# U_I_Meter_TOP.net
KiCad netlist of a schematic drawn in Altium Designer
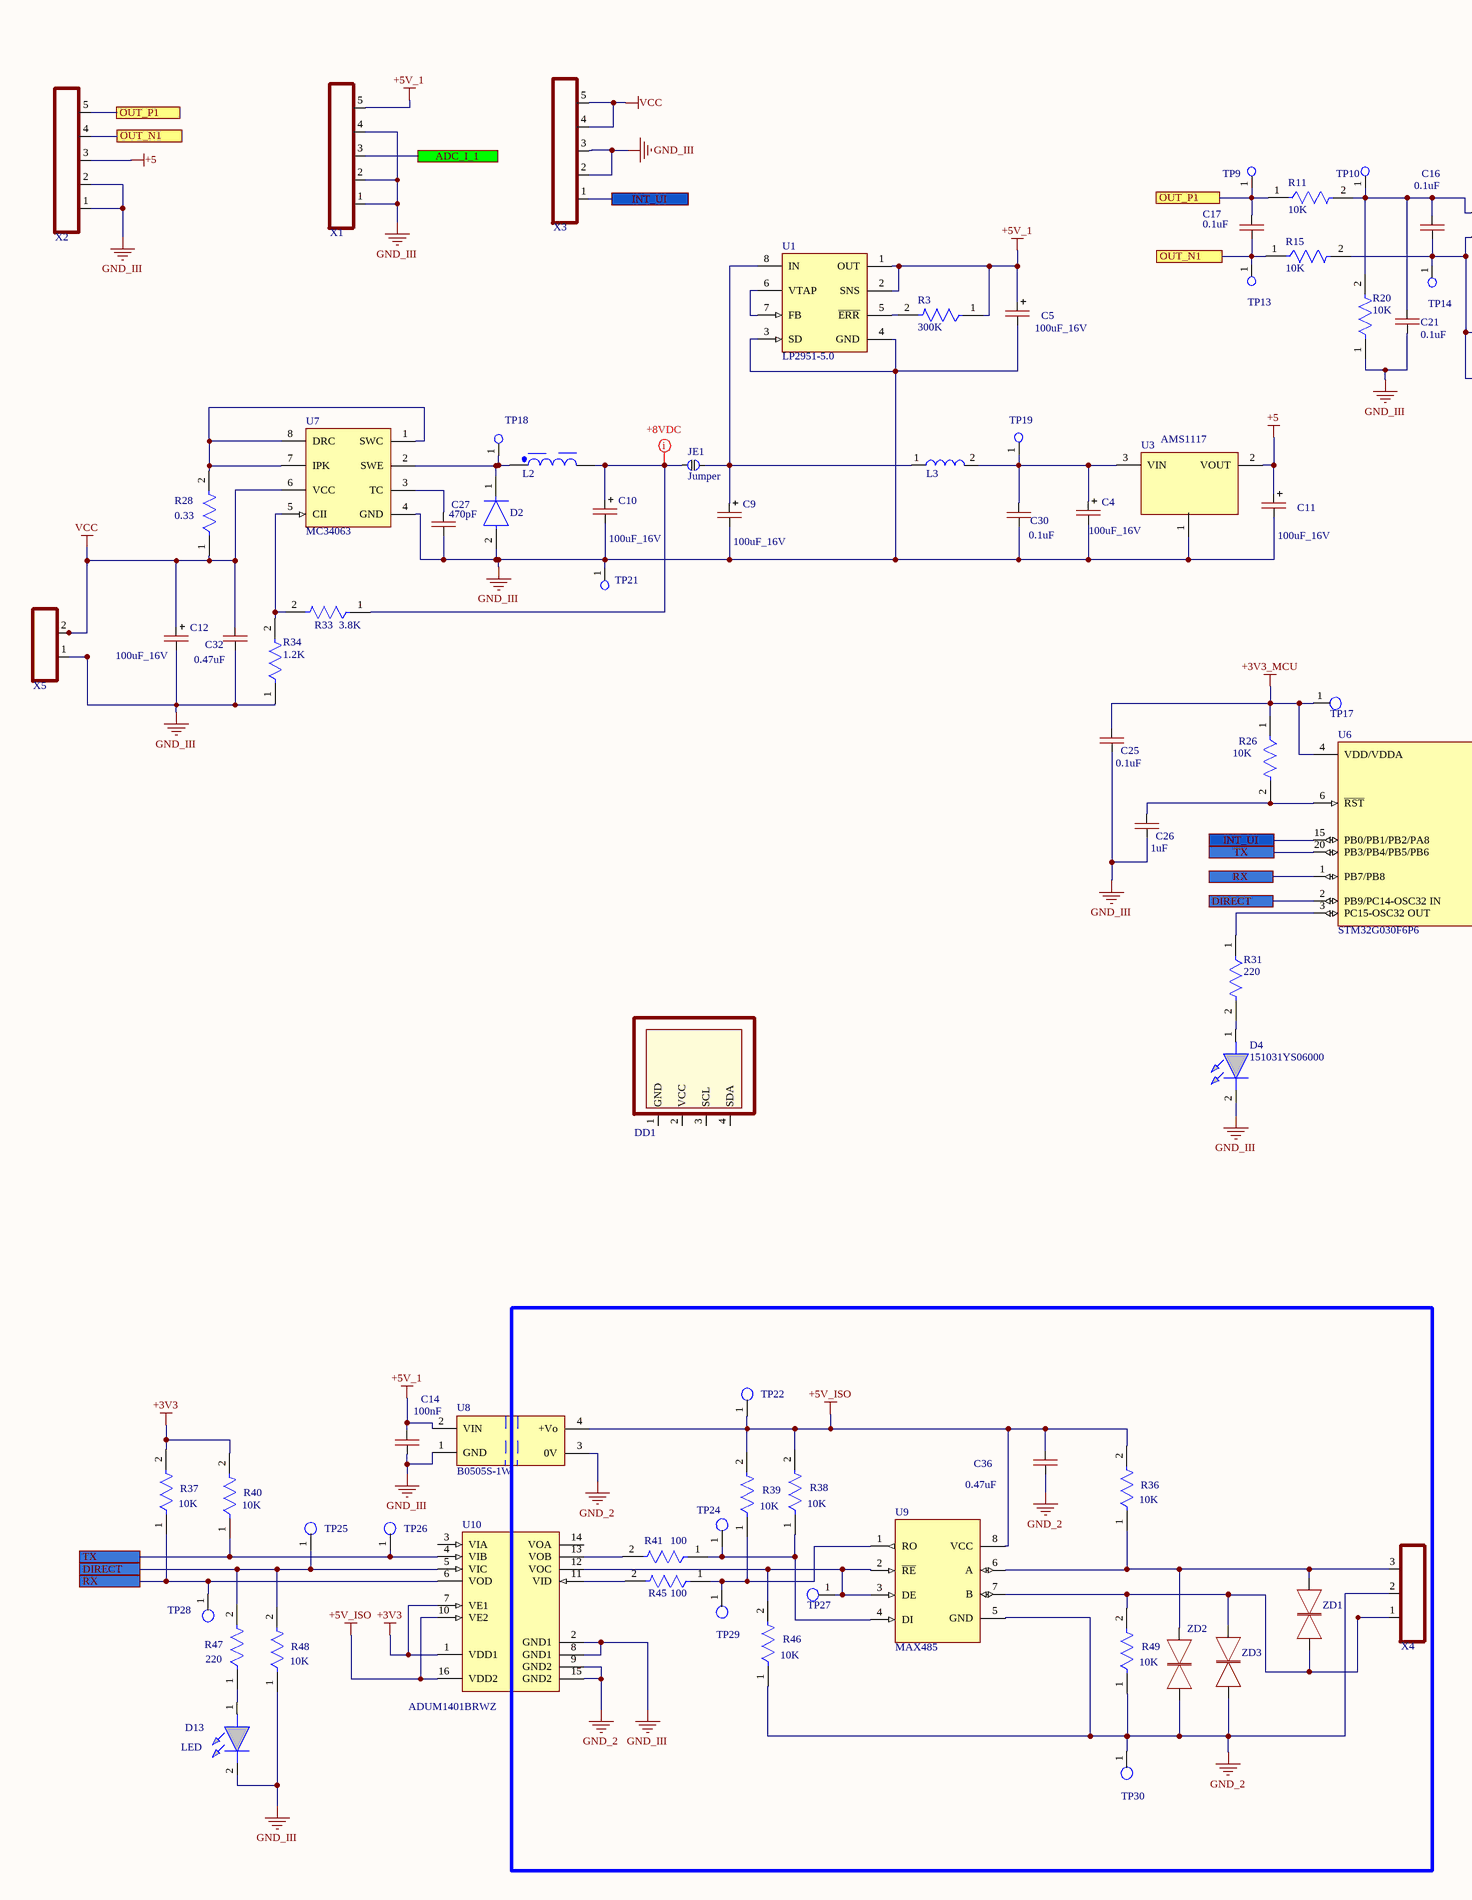
[diagram p0: U_I_Meter_TOP.SchDoc, left]
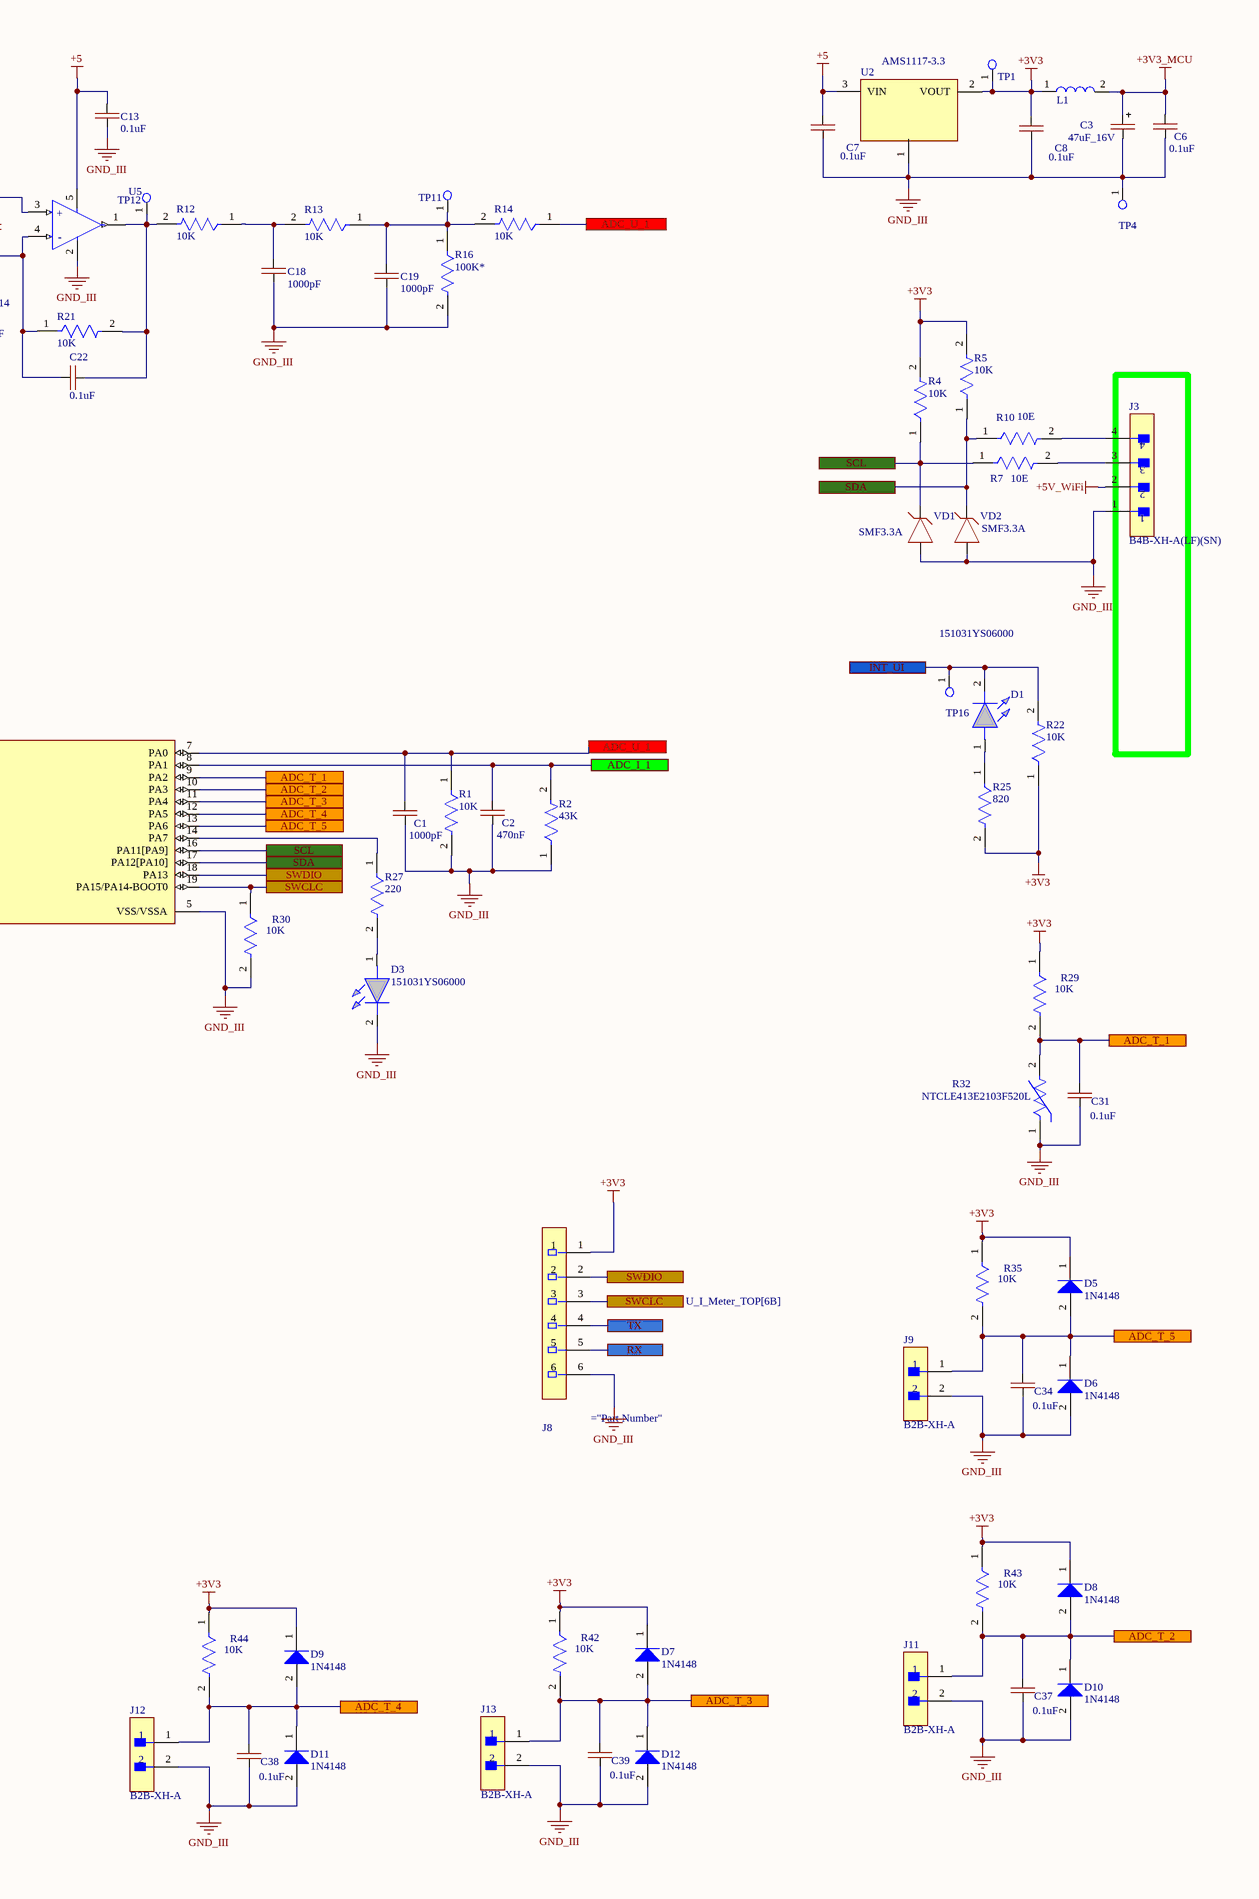
[diagram p1: U_I_Meter_TOP.SchDoc, right]

(export (version "E")
  (design (tool "Eeschema 10.0.6"))
  (components
    (comp (ref "C1")
      (value "1000pF")
      (footprint "CAP-0805")
      (libsource (lib "PASSIVE_COMPONENTS") (part "CAP-NON-POLAR"))
    )
    (comp (ref "C2")
      (value "470nF")
      (footprint "CAP-0805")
      (libsource (lib "PASSIVE_COMPONENTS") (part "CAP-NON-POLAR"))
    )
    (comp (ref "C3")
      (value "47uF_16V")
      (footprint "CAP-TAN-D")
      (libsource (lib "PASSIVE_COMPONENTS") (part "CAP-POLAR"))
    )
    (comp (ref "C4")
      (value "100uF_16V")
      (footprint "CAP-TAN-D")
      (libsource (lib "PASSIVE_COMPONENTS") (part "CAP_POL_SMD"))
    )
    (comp (ref "C5")
      (value "100uF_16V")
      (footprint "CAP-TAN-D")
      (libsource (lib "PASSIVE_COMPONENTS") (part "CAP_POL_SMD"))
    )
    (comp (ref "C6")
      (value "0.1uF")
      (footprint "CAP-0805")
      (libsource (lib "PASSIVE_COMPONENTS") (part "CAP-NON-POLAR"))
    )
    (comp (ref "C7")
      (value "0.1uF")
      (footprint "CAP-0805")
      (libsource (lib "PASSIVE_COMPONENTS") (part "CAP-NON-POLAR"))
    )
    (comp (ref "C8")
      (value "0.1uF")
      (footprint "CAP-0805")
      (libsource (lib "PASSIVE_COMPONENTS") (part "CAP-NON-POLAR"))
    )
    (comp (ref "C9")
      (value "100uF_16V")
      (footprint "CAP-TAN-D")
      (libsource (lib "PASSIVE_COMPONENTS") (part "CAP_POL_SMD"))
    )
    (comp (ref "C10")
      (value "100uF_16V")
      (footprint "CAP-TAN-D")
      (libsource (lib "PASSIVE_COMPONENTS") (part "CAP_POL_SMD"))
    )
    (comp (ref "C11")
      (value "100uF_16V")
      (footprint "CAP-TAN-D")
      (libsource (lib "PASSIVE_COMPONENTS") (part "CAP_POL_SMD"))
    )
    (comp (ref "C12")
      (value "100uF_16V")
      (footprint "CAP-TAN-D")
      (libsource (lib "PASSIVE_COMPONENTS") (part "CAP_POL_SMD"))
    )
    (comp (ref "C13")
      (value "0.1uF")
      (footprint "CAP-0805")
      (libsource (lib "PASSIVE_COMPONENTS") (part "CAP-NON-POLAR"))
    )
    (comp (ref "C14")
      (value "100nF")
      (footprint "CAP-0805")
      (libsource (lib "PASSIVE_COMPONENTS") (part "CAP-NON-POLAR"))
    )
    (comp (ref "C16")
      (value "0.1uF")
      (footprint "CAP-0805")
      (libsource (lib "PASSIVE_COMPONENTS") (part "CAP-NON-POLAR"))
    )
    (comp (ref "C17")
      (value "0.1uF")
      (footprint "CAP-0805")
      (libsource (lib "PASSIVE_COMPONENTS") (part "CAP-NON-POLAR"))
    )
    (comp (ref "C18")
      (value "1000pF")
      (footprint "CAP-0805")
      (libsource (lib "PASSIVE_COMPONENTS") (part "CAP-NON-POLAR"))
    )
    (comp (ref "C19")
      (value "1000pF")
      (footprint "CAP-0805")
      (libsource (lib "PASSIVE_COMPONENTS") (part "CAP-NON-POLAR"))
    )
    (comp (ref "C21")
      (value "0.1uF")
      (footprint "CAP-0805")
      (libsource (lib "PASSIVE_COMPONENTS") (part "CAP-NON-POLAR"))
    )
    (comp (ref "C22")
      (value "0.1uF")
      (footprint "CAP-0805")
      (libsource (lib "PASSIVE_COMPONENTS") (part "CAP-NON-POLAR"))
    )
    (comp (ref "C25")
      (value "0.1uF")
      (footprint "CAP-0805")
      (libsource (lib "PASSIVE_COMPONENTS") (part "CAP-NON-POLAR"))
    )
    (comp (ref "C26")
      (value "1uF")
      (footprint "CAP-0805")
      (libsource (lib "PASSIVE_COMPONENTS") (part "CAP-NON-POLAR"))
    )
    (comp (ref "C27")
      (value "470pF")
      (footprint "CAP-0805")
      (libsource (lib "PASSIVE_COMPONENTS") (part "CAP-NON-POLAR"))
    )
    (comp (ref "C30")
      (value "0.1uF")
      (footprint "CAP-0805")
      (libsource (lib "PASSIVE_COMPONENTS") (part "CAP-NON-POLAR"))
    )
    (comp (ref "C31")
      (value "0.1uF")
      (footprint "CAP-0805")
      (libsource (lib "PASSIVE_COMPONENTS") (part "CAP-NON-POLAR"))
    )
    (comp (ref "C32")
      (value "0.47uF")
      (footprint "CAP-0805")
      (libsource (lib "PASSIVE_COMPONENTS") (part "CAP-NON-POLAR"))
    )
    (comp (ref "C34")
      (value "0.1uF")
      (footprint "CAP-0805")
      (libsource (lib "PASSIVE_COMPONENTS") (part "CAP-NON-POLAR"))
    )
    (comp (ref "C36")
      (value "0.47uF")
      (footprint "CAP-0805")
      (libsource (lib "PASSIVE_COMPONENTS") (part "CAP-NON-POLAR"))
    )
    (comp (ref "C37")
      (value "0.1uF")
      (footprint "CAP-0805")
      (libsource (lib "PASSIVE_COMPONENTS") (part "CAP-NON-POLAR"))
    )
    (comp (ref "C38")
      (value "0.1uF")
      (footprint "CAP-0805")
      (libsource (lib "PASSIVE_COMPONENTS") (part "CAP-NON-POLAR"))
    )
    (comp (ref "C39")
      (value "0.1uF")
      (footprint "CAP-0805")
      (libsource (lib "PASSIVE_COMPONENTS") (part "CAP-NON-POLAR"))
    )
    (comp (ref "D1")
      (value "151031YS06000")
      (footprint "LED_3mm_BLUE")
      (description "WURTH ELEKTRONIK - 151031YS06000 - LED, Yellow, Through Hole, T-1 (3mm), 30 mA, 2 V, 590 nm")
      (fields (field (name "MOUSER PART NUMBER") "710-151031YS06000"))
      (libsource (lib "Optic-LED") (part "LED"))
    )
    (comp (ref "D2")
      (value "ES1G")
      (footprint "FP-403AE-MFG")
      (description "Ultrafast")
      (libsource (lib "Diodes") (part "ES1G"))
    )
    (comp (ref "D3")
      (value "151031YS06000")
      (footprint "LED_3mm_GREEN")
      (description "WURTH ELEKTRONIK - 151031YS06000 - LED, Yellow, Through Hole, T-1 (3mm), 30 mA, 2 V, 590 nm")
      (fields (field (name "MOUSER PART NUMBER") "710-151031YS06000"))
      (libsource (lib "Optic-LED") (part "LED"))
    )
    (comp (ref "D4")
      (value "151031YS06000")
      (footprint "LED_3mm_RED")
      (description "WURTH ELEKTRONIK - 151031YS06000 - LED, Yellow, Through Hole, T-1 (3mm), 30 mA, 2 V, 590 nm")
      (fields (field (name "MOUSER PART NUMBER") "710-151031YS06000"))
      (libsource (lib "Optic-LED") (part "LED"))
    )
    (comp (ref "D5")
      (value "1N4148")
      (footprint "DIOD-SOD123-2_V")
      (libsource (lib "Diodes") (part "1N4148"))
    )
    (comp (ref "D6")
      (value "1N4148")
      (footprint "DIOD-SOD123-2_V")
      (libsource (lib "Diodes") (part "1N4148"))
    )
    (comp (ref "D7")
      (value "1N4148")
      (footprint "DIOD-SOD123-2_V")
      (libsource (lib "Diodes") (part "1N4148"))
    )
    (comp (ref "D8")
      (value "1N4148")
      (footprint "DIOD-SOD123-2_V")
      (libsource (lib "Diodes") (part "1N4148"))
    )
    (comp (ref "D9")
      (value "1N4148")
      (footprint "DIOD-SOD123-2_V")
      (libsource (lib "Diodes") (part "1N4148"))
    )
    (comp (ref "D10")
      (value "1N4148")
      (footprint "DIOD-SOD123-2_V")
      (libsource (lib "Diodes") (part "1N4148"))
    )
    (comp (ref "D11")
      (value "1N4148")
      (footprint "DIOD-SOD123-2_V")
      (libsource (lib "Diodes") (part "1N4148"))
    )
    (comp (ref "D12")
      (value "1N4148")
      (footprint "DIOD-SOD123-2_V")
      (libsource (lib "Diodes") (part "1N4148"))
    )
    (comp (ref "D13")
      (value "LED")
      (footprint "LED_3mm_BLUE")
      (description "WURTH ELEKTRONIK - 151031YS06000 - LED, Yellow, Through Hole, T-1 (3mm), 30 mA, 2 V, 590 nm")
      (fields
        (field (name "MANUFACTURER_PART_NUMBER") "151031YS06000")
        (field (name "MOUSER PART NUMBER") "710-151031YS06000")
      )
      (libsource (lib "Optic-LED") (part "LED"))
    )
    (comp (ref "DD1")
      (value "OLED_SSD_1306")
      (footprint "OLED_128x64_SSD_1306")
      (libsource (lib "Displays") (part "OLED_SSD_1306"))
    )
    (comp (ref "J3")
      (value "B4B-XH-A(LF)(SN)")
      (footprint "B4B-XH-A")
      (libsource (lib "Connectors") (part "B4B-XH-A(LF)(SN)"))
    )
    (comp (ref "J8")
      (value "SWR25X-NRTC-S06-ST-BA")
      (footprint "Sullins_SWR25X-NRTC-S06-ST-BA_MFG")
      (libsource (lib "Conn_Sullins_SWR25X-NRTC-S06-ST-BA_eec") (part "SWR25X-NRTC-S06-ST-BA"))
    )
    (comp (ref "J9")
      (value "B2B-XH-A")
      (footprint "B2B-XH-A")
      (libsource (lib "Connectors") (part "B2B-XH-A"))
    )
    (comp (ref "J11")
      (value "B2B-XH-A")
      (footprint "B2B-XH-A")
      (libsource (lib "Connectors") (part "B2B-XH-A"))
    )
    (comp (ref "J12")
      (value "B2B-XH-A")
      (footprint "B2B-XH-A")
      (libsource (lib "Connectors") (part "B2B-XH-A"))
    )
    (comp (ref "J13")
      (value "B2B-XH-A")
      (footprint "B2B-XH-A")
      (libsource (lib "Connectors") (part "B2B-XH-A"))
    )
    (comp (ref "JE1") (value "Jumper") (footprint "JE") (libsource (lib "Connectors") (part "JE")))
    (comp (ref "L1")
      (value "Coil")
      (footprint "Coil_4.5x4.5_mm")
      (libsource (lib "Transformers") (part "Coil"))
    )
    (comp (ref "L2")
      (value "3.3µH, 4A")
      (footprint "WE-PD2_5848")
      (description "WE-PD2 SMT Power Inductor, size 5848, 3.3µH, 4A, 0.06Ω")
      (fields
        (field (name "MANUFACTURER PART NUMBER") "744774033")
        (field (name "MANUFACTURER") "Wurth Elektronik")
      )
      (libsource (lib "WE-PD2 (rev22d)") (part "744774033"))
    )
    (comp (ref "L3")
      (value "Coil")
      (footprint "Coil_4.5x4.5_mm")
      (libsource (lib "Transformers") (part "Coil"))
    )
    (comp (ref "R1")
      (value "10K")
      (footprint "RES-0805")
      (libsource (lib "PASSIVE_COMPONENTS") (part "RES-CONST"))
    )
    (comp (ref "R2")
      (value "43K")
      (footprint "RES-0805")
      (libsource (lib "PASSIVE_COMPONENTS") (part "RES-CONST"))
    )
    (comp (ref "R3")
      (value "300K")
      (footprint "RES-0805")
      (libsource (lib "PASSIVE_COMPONENTS") (part "RES-CONST"))
    )
    (comp (ref "R4")
      (value "10K")
      (footprint "RES-0805")
      (libsource (lib "PASSIVE_COMPONENTS") (part "RES-CONST"))
    )
    (comp (ref "R5")
      (value "10K")
      (footprint "RES-0805")
      (libsource (lib "PASSIVE_COMPONENTS") (part "RES-CONST"))
    )
    (comp (ref "R7")
      (value "10E")
      (footprint "RES-0805")
      (libsource (lib "PASSIVE_COMPONENTS") (part "RES-CONST"))
    )
    (comp (ref "R10")
      (value "10E")
      (footprint "RES-0805")
      (libsource (lib "PASSIVE_COMPONENTS") (part "RES-CONST"))
    )
    (comp (ref "R11")
      (value "10K")
      (footprint "RES-0805")
      (libsource (lib "PASSIVE_COMPONENTS") (part "RES-CONST"))
    )
    (comp (ref "R12")
      (value "10K")
      (footprint "RES-0805")
      (libsource (lib "PASSIVE_COMPONENTS") (part "RES-CONST"))
    )
    (comp (ref "R13")
      (value "10K")
      (footprint "RES-0805")
      (libsource (lib "PASSIVE_COMPONENTS") (part "RES-CONST"))
    )
    (comp (ref "R14")
      (value "10K")
      (footprint "RES-0805")
      (libsource (lib "PASSIVE_COMPONENTS") (part "RES-CONST"))
    )
    (comp (ref "R15")
      (value "10K")
      (footprint "RES-0805")
      (libsource (lib "PASSIVE_COMPONENTS") (part "RES-CONST"))
    )
    (comp (ref "R16")
      (value "100K*")
      (footprint "RES-0805")
      (libsource (lib "PASSIVE_COMPONENTS") (part "RES-CONST"))
    )
    (comp (ref "R20")
      (value "10K")
      (footprint "RES-0805")
      (libsource (lib "PASSIVE_COMPONENTS") (part "RES-CONST"))
    )
    (comp (ref "R21")
      (value "10K")
      (footprint "RES-0805")
      (libsource (lib "PASSIVE_COMPONENTS") (part "RES-CONST"))
    )
    (comp (ref "R22")
      (value "10K")
      (footprint "RES-0805")
      (libsource (lib "PASSIVE_COMPONENTS") (part "RES-CONST"))
    )
    (comp (ref "R25")
      (value "820")
      (footprint "RES-0805")
      (description "220")
      (libsource (lib "PASSIVE_COMPONENTS") (part "RES-CONST"))
    )
    (comp (ref "R26")
      (value "10K")
      (footprint "RES-0805")
      (libsource (lib "PASSIVE_COMPONENTS") (part "RES-CONST"))
    )
    (comp (ref "R27")
      (value "220")
      (footprint "RES-0805")
      (libsource (lib "PASSIVE_COMPONENTS") (part "RES-CONST"))
    )
    (comp (ref "R28")
      (value "0.33")
      (footprint "RES-1206")
      (libsource (lib "PASSIVE_COMPONENTS") (part "RES-CONST"))
    )
    (comp (ref "R29")
      (value "10K")
      (footprint "RES-0805")
      (libsource (lib "PASSIVE_COMPONENTS") (part "RES-CONST"))
    )
    (comp (ref "R30")
      (value "10K")
      (footprint "RES-0805")
      (libsource (lib "PASSIVE_COMPONENTS") (part "RES-CONST"))
    )
    (comp (ref "R31")
      (value "220")
      (footprint "RES-0805")
      (libsource (lib "PASSIVE_COMPONENTS") (part "RES-CONST"))
    )
    (comp (ref "R32")
      (value "NTCLE413E2103F520L")
      (footprint "FP-NTCLE413E2103F520L-MFG")
      (description "THERMISTOR NTC 10KOHM 3435K BEAD")
      (fields (field (name "TOLERANCE") "1%"))
      (libsource (lib "Altium Content Vault") (part "3b148a6ebabc5fb4d708a66c052d352"))
    )
    (comp (ref "R33")
      (value "3.8K")
      (footprint "RES-0805")
      (description "10K")
      (libsource (lib "PASSIVE_COMPONENTS") (part "RES-CONST"))
    )
    (comp (ref "R34")
      (value "1.2K")
      (footprint "RES-0805")
      (libsource (lib "PASSIVE_COMPONENTS") (part "RES-CONST"))
    )
    (comp (ref "R35")
      (value "10K")
      (footprint "RES-0805")
      (libsource (lib "PASSIVE_COMPONENTS") (part "RES-CONST"))
    )
    (comp (ref "R36")
      (value "10K")
      (footprint "RES-0805")
      (libsource (lib "PASSIVE_COMPONENTS") (part "RES-CONST"))
    )
    (comp (ref "R37")
      (value "10K")
      (footprint "RES-0805")
      (libsource (lib "PASSIVE_COMPONENTS") (part "RES-CONST"))
    )
    (comp (ref "R38")
      (value "10K")
      (footprint "RES-0805")
      (libsource (lib "PASSIVE_COMPONENTS") (part "RES-CONST"))
    )
    (comp (ref "R39")
      (value "10K")
      (footprint "RES-0805")
      (libsource (lib "PASSIVE_COMPONENTS") (part "RES-CONST"))
    )
    (comp (ref "R40")
      (value "10K")
      (footprint "RES-0805")
      (libsource (lib "PASSIVE_COMPONENTS") (part "RES-CONST"))
    )
    (comp (ref "R41")
      (value "100")
      (footprint "RES-0805")
      (libsource (lib "PASSIVE_COMPONENTS") (part "RES-CONST"))
    )
    (comp (ref "R42")
      (value "10K")
      (footprint "RES-0805")
      (libsource (lib "PASSIVE_COMPONENTS") (part "RES-CONST"))
    )
    (comp (ref "R43")
      (value "10K")
      (footprint "RES-0805")
      (libsource (lib "PASSIVE_COMPONENTS") (part "RES-CONST"))
    )
    (comp (ref "R44")
      (value "10K")
      (footprint "RES-0805")
      (libsource (lib "PASSIVE_COMPONENTS") (part "RES-CONST"))
    )
    (comp (ref "R45")
      (value "100")
      (footprint "RES-0805")
      (libsource (lib "PASSIVE_COMPONENTS") (part "RES-CONST"))
    )
    (comp (ref "R46")
      (value "10K")
      (footprint "RES-0805")
      (libsource (lib "PASSIVE_COMPONENTS") (part "RES-CONST"))
    )
    (comp (ref "R47")
      (value "220")
      (footprint "RES-0805")
      (libsource (lib "PASSIVE_COMPONENTS") (part "RES-CONST"))
    )
    (comp (ref "R48")
      (value "10K")
      (footprint "RES-0805")
      (libsource (lib "PASSIVE_COMPONENTS") (part "RES-CONST"))
    )
    (comp (ref "R49")
      (value "10K")
      (footprint "RES-0805")
      (libsource (lib "PASSIVE_COMPONENTS") (part "RES-CONST"))
    )
    (comp (ref "TP1")
      (value "Test_Point_PCB")
      (footprint "Test_Point")
      (description "Test_Point")
      (libsource (lib "Connectors") (part "TP_PCB?"))
    )
    (comp (ref "TP4")
      (value "Test_Point_PCB")
      (footprint "Pin_Test_Point(Pink)")
      (description "Test_Point")
      (libsource (lib "Connectors") (part "TP_PCB?"))
    )
    (comp (ref "TP9")
      (value "Test_Point_PCB")
      (footprint "Test_Point")
      (description "Test_Point")
      (libsource (lib "Connectors") (part "TP_PCB?"))
    )
    (comp (ref "TP10")
      (value "Test_Point_PCB")
      (footprint "Test_Point")
      (description "Test_Point")
      (libsource (lib "Connectors") (part "TP_PCB?"))
    )
    (comp (ref "TP11")
      (value "Test_Point_PCB")
      (footprint "Test_Point")
      (description "Test_Point")
      (libsource (lib "Connectors") (part "TP_PCB?"))
    )
    (comp (ref "TP12")
      (value "Test_Point_PCB")
      (footprint "Test_Point")
      (description "Test_Point")
      (libsource (lib "Connectors") (part "TP_PCB?"))
    )
    (comp (ref "TP13")
      (value "Test_Point_PCB")
      (footprint "Test_Point")
      (description "Test_Point")
      (libsource (lib "Connectors") (part "TP_PCB?"))
    )
    (comp (ref "TP14")
      (value "Test_Point_PCB")
      (footprint "Test_Point")
      (description "Test_Point")
      (libsource (lib "Connectors") (part "TP_PCB?"))
    )
    (comp (ref "TP16")
      (value "Test_Point_PCB")
      (footprint "Test_Point")
      (description "Test_Point")
      (libsource (lib "Connectors") (part "TP_PCB?"))
    )
    (comp (ref "TP17")
      (value "~")
      (footprint "Test_Point")
      (description "Test_Point")
      (libsource (lib "") (part "TP_PCB?_1"))
    )
    (comp (ref "TP18")
      (value "Test_Point_PCB")
      (footprint "Test_Point")
      (description "Test_Point")
      (libsource (lib "Connectors") (part "TP_PCB?"))
    )
    (comp (ref "TP19")
      (value "Test_Point_PCB")
      (footprint "Test_Point")
      (description "Test_Point")
      (libsource (lib "Connectors") (part "TP_PCB?"))
    )
    (comp (ref "TP21")
      (value "Test_Point_PCB")
      (footprint "Pin_Test_Point(Orange)")
      (description "Test_Point")
      (libsource (lib "Connectors") (part "TP_PCB?"))
    )
    (comp (ref "TP22")
      (value "Test_Point_PCB")
      (footprint "Test_Point")
      (description "Test_Point")
      (libsource (lib "Test_Point") (part "TP_PCB?"))
    )
    (comp (ref "TP24")
      (value "Test_Point_PCB")
      (footprint "Test_Point")
      (description "Test_Point")
      (libsource (lib "Test_Point") (part "TP_PCB?"))
    )
    (comp (ref "TP25")
      (value "Test_Point_PCB")
      (footprint "Test_Point")
      (description "Test_Point")
      (libsource (lib "Test_Point") (part "TP_PCB?"))
    )
    (comp (ref "TP26")
      (value "Test_Point_PCB")
      (footprint "Test_Point")
      (description "Test_Point")
      (libsource (lib "Test_Point") (part "TP_PCB?"))
    )
    (comp (ref "TP27")
      (value "Test_Point_PCB")
      (footprint "Test_Point")
      (description "Test_Point")
      (libsource (lib "Test_Point") (part "TP_PCB?"))
    )
    (comp (ref "TP28")
      (value "Test_Point_PCB")
      (footprint "Test_Point")
      (description "Test_Point")
      (libsource (lib "Test_Point") (part "TP_PCB?"))
    )
    (comp (ref "TP29")
      (value "~")
      (footprint "Test_Point")
      (description "Test_Point")
      (libsource (lib "") (part "TP_PCB?_1"))
    )
    (comp (ref "TP30")
      (value "Test_Point_PCB")
      (footprint "Test_Point")
      (description "Test_Point")
      (libsource (lib "Test_Point") (part "TP_PCB?"))
    )
    (comp (ref "U1")
      (value "LP2951-5.0")
      (footprint "SOIC-8_L")
      (libsource (lib "Integrated_Circuts") (part "LP2951-3.3"))
    )
    (comp (ref "U2")
      (value "AMS1117-3.3")
      (footprint "SOT-223")
      (libsource (lib "Integrated_Circuts") (part "AMS1117"))
    )
    (comp (ref "U3")
      (value "AMS1117")
      (footprint "SOT-89")
      (libsource (lib "Integrated_Circuts") (part "AMS1117"))
    )
    (comp (ref "U5")
      (value "~")
      (footprint "SOT-23-5")
      (description "IC OPAMP GP 1 CIRCUIT SOT23-5")
      (fields (field (name "VOLTAGE") "6V"))
      (libsource (lib "Integrated_Circuts") (part "MCP6001T"))
    )
    (comp (ref "U6")
      (value "STM32G030F6P6")
      (footprint "FP-TSSOP20-YA-IPC_A")
      (description "SOIC-20")
      (libsource (lib "Integrated_Circuts") (part "STM32G030F6P6"))
    )
    (comp (ref "U7")
      (value "MC34063")
      (footprint "SOIC-8_M")
      (libsource (lib "Integrated_Circuts") (part "MC34063"))
    )
    (comp (ref "U8")
      (value "B0505S-1W")
      (footprint "B0505S-1W")
      (libsource (lib "Integrated_Circuts") (part "B0505S-1W"))
    )
    (comp (ref "U9")
      (value "MAX485")
      (footprint "SOIC-8-MFG")
      (libsource (lib "Integrated_Circuts") (part "MAX485"))
    )
    (comp (ref "U10")
      (value "ADUM1401BRWZ")
      (footprint "ADI-RW-16_M")
      (fields (field (name "MANUFACTURER") "Analog Devices"))
      (libsource (lib "Altium Content Vault") (part "ADI-ADUMX4X1-16"))
    )
    (comp (ref "VD1")
      (value "SMF3.3A")
      (footprint "SMF3.3A")
      (libsource (lib "Diodes") (part "ESD_Unidirect"))
    )
    (comp (ref "VD2")
      (value "SMF3.3A")
      (footprint "SMF3.3A")
      (libsource (lib "Diodes") (part "ESD_Unidirect"))
    )
    (comp (ref "X1")
      (value "CONN-5-PIN")
      (footprint "CONN-PLS-5-2.54_2")
      (libsource (lib "PLS-5__") (part "CONN-5-PIN"))
    )
    (comp (ref "X2")
      (value "CONN-5-PIN")
      (footprint "CONN-PLS-5-2.54_2")
      (libsource (lib "PLS-5__") (part "CONN-5-PIN"))
    )
    (comp (ref "X3")
      (value "CONN-5-PIN")
      (footprint "CONN-PLS-5-2.54_2")
      (libsource (lib "PLS-5__") (part "CONN-5-PIN"))
    )
    (comp (ref "X4")
      (value "CONN-3-PIN")
      (footprint "691305340003")
      (libsource (lib "691305340003") (part "CONN-3-PIN"))
    )
    (comp (ref "X5")
      (value "CONN-2-PIN")
      (footprint "691305340002")
      (libsource (lib "691305340003") (part "CONN-2-PIN"))
    )
    (comp (ref "ZD1")
      (value "P6SMB16CA")
      (footprint "DO-214AA")
      (libsource (lib "P6SMB16CA") (part "P6SMB16CA"))
    )
    (comp (ref "ZD2")
      (value "P6SMB16CA")
      (footprint "DO-214AA")
      (libsource (lib "P6SMB16CA") (part "P6SMB16CA"))
    )
    (comp (ref "ZD3")
      (value "P6SMB16CA")
      (footprint "DO-214AA")
      (libsource (lib "P6SMB16CA") (part "P6SMB16CA"))
    )
  )
  (nets
    (net (code "1") (name "+3V3") (class "Default")
      (node (ref "C8") (pin "2") (pinfunction "2_2") (pintype "passive"))
      (node (ref "D5") (pin "1") (pinfunction "K_1") (pintype "passive"))
      (node (ref "D7") (pin "1") (pinfunction "K_1") (pintype "passive"))
      (node (ref "D8") (pin "1") (pinfunction "K_1") (pintype "passive"))
      (node (ref "D9") (pin "1") (pinfunction "K_1") (pintype "passive"))
      (node (ref "J8") (pin "1") (pinfunction "1_1") (pintype "passive"))
      (node (ref "L1") (pin "1") (pinfunction "1_1") (pintype "passive"))
      (node (ref "R22") (pin "1") (pinfunction "1_1") (pintype "passive"))
      (node (ref "R25") (pin "2") (pinfunction "2_2") (pintype "passive"))
      (node (ref "R29") (pin "1") (pinfunction "1_1") (pintype "passive"))
      (node (ref "R35") (pin "1") (pinfunction "1_1") (pintype "passive"))
      (node (ref "R37") (pin "2") (pinfunction "2_2") (pintype "passive"))
      (node (ref "R4") (pin "2") (pinfunction "2_2") (pintype "passive"))
      (node (ref "R40") (pin "2") (pinfunction "2_2") (pintype "passive"))
      (node (ref "R42") (pin "1") (pinfunction "1_1") (pintype "passive"))
      (node (ref "R43") (pin "1") (pinfunction "1_1") (pintype "passive"))
      (node (ref "R44") (pin "1") (pinfunction "1_1") (pintype "passive"))
      (node (ref "R5") (pin "2") (pinfunction "2_2") (pintype "passive"))
      (node (ref "TP1") (pin "1") (pinfunction "G9_1") (pintype "passive"))
      (node (ref "U10") (pin "1") (pinfunction "VDD1_1") (pintype "power_in"))
      (node (ref "U10") (pin "7") (pinfunction "VE1_7") (pintype "input"))
      (node (ref "U2") (pin "2") (pinfunction "VOUT_2") (pintype "passive"))
    )
    (net (code "2") (name "+3V3_MCU") (class "Default")
      (node (ref "C25") (pin "2") (pinfunction "2_2") (pintype "passive"))
      (node (ref "C3") (pin "1") (pinfunction "+_1") (pintype "passive"))
      (node (ref "C6") (pin "2") (pinfunction "2_2") (pintype "passive"))
      (node (ref "L1") (pin "2") (pinfunction "2_2") (pintype "passive"))
      (node (ref "R26") (pin "1") (pinfunction "1_1") (pintype "passive"))
      (node (ref "TP17") (pin "1") (pinfunction "G9_1") (pintype "passive"))
      (node (ref "U6") (pin "4") (pinfunction "VDD/VDDA_4") (pintype "power_in"))
    )
    (net (code "3") (name "+5") (class "Default")
      (node (ref "C11") (pin "1") (pinfunction "+_1") (pintype "passive"))
      (node (ref "C13") (pin "2") (pinfunction "2_2") (pintype "passive"))
      (node (ref "C7") (pin "2") (pinfunction "2_2") (pintype "passive"))
      (node (ref "U2") (pin "3") (pinfunction "VIN_3") (pintype "power_in"))
      (node (ref "U3") (pin "2") (pinfunction "VOUT_2") (pintype "passive"))
      (node (ref "U5") (pin "5") (pinfunction "VDD_5") (pintype "power_in"))
      (node (ref "X2") (pin "3") (pinfunction "3_3") (pintype "passive"))
    )
    (net (code "4") (name "+5V_1") (class "Default")
      (node (ref "C14") (pin "2") (pinfunction "2_2") (pintype "passive"))
      (node (ref "C5") (pin "1") (pinfunction "+_1") (pintype "passive"))
      (node (ref "R3") (pin "1") (pinfunction "1_1") (pintype "passive"))
      (node (ref "U1") (pin "1") (pinfunction "OUT_1") (pintype "power_in"))
      (node (ref "U1") (pin "2") (pinfunction "SNS_2") (pintype "passive"))
      (node (ref "U8") (pin "2") (pinfunction "VIN_2") (pintype "power_in"))
      (node (ref "X1") (pin "5") (pinfunction "5_5") (pintype "passive"))
    )
    (net (code "5") (name "+5V_ISO") (class "Default")
      (node (ref "C36") (pin "1") (pinfunction "1_1") (pintype "passive"))
      (node (ref "R36") (pin "2") (pinfunction "2_2") (pintype "passive"))
      (node (ref "R38") (pin "2") (pinfunction "2_2") (pintype "passive"))
      (node (ref "R39") (pin "2") (pinfunction "2_2") (pintype "passive"))
      (node (ref "TP22") (pin "1") (pinfunction "G9_1") (pintype "passive"))
      (node (ref "U10") (pin "10") (pinfunction "VE2_10") (pintype "input"))
      (node (ref "U10") (pin "16") (pinfunction "VDD2_16") (pintype "power_in"))
      (node (ref "U8") (pin "4") (pinfunction "+Vo_4") (pintype "power_in"))
      (node (ref "U9") (pin "8") (pinfunction "VCC_8") (pintype "power_in"))
    )
    (net (code "6") (name "+5V_WiFi") (class "Default")
      (node (ref "J3") (pin "2") (pinfunction "2_2") (pintype "passive"))
    )
    (net (code "7") (name "/ADC_I_1") (class "Default")
      (node (ref "C2") (pin "2") (pinfunction "2_2") (pintype "passive"))
      (node (ref "R2") (pin "2") (pinfunction "2_2") (pintype "passive"))
      (node (ref "U6") (pin "8") (pinfunction "PA1_8") (pintype "bidirectional"))
      (node (ref "X1") (pin "3") (pinfunction "3_3") (pintype "passive"))
    )
    (net (code "8") (name "/ADC_T_1") (class "Default")
      (node (ref "C31") (pin "2") (pinfunction "2_2") (pintype "passive"))
      (node (ref "R29") (pin "2") (pinfunction "2_2") (pintype "passive"))
      (node (ref "R32") (pin "2") (pinfunction "2_2") (pintype "passive"))
      (node (ref "U6") (pin "9") (pinfunction "PA2_9") (pintype "bidirectional"))
    )
    (net (code "9") (name "/ADC_T_2") (class "Default")
      (node (ref "C37") (pin "2") (pinfunction "2_2") (pintype "passive"))
      (node (ref "D10") (pin "1") (pinfunction "K_1") (pintype "passive"))
      (node (ref "D8") (pin "2") (pinfunction "A_2") (pintype "passive"))
      (node (ref "J11") (pin "1") (pinfunction "1_1") (pintype "passive"))
      (node (ref "R43") (pin "2") (pinfunction "2_2") (pintype "passive"))
      (node (ref "U6") (pin "10") (pinfunction "PA3_10") (pintype "bidirectional"))
    )
    (net (code "10") (name "/ADC_T_3") (class "Default")
      (node (ref "C39") (pin "2") (pinfunction "2_2") (pintype "passive"))
      (node (ref "D12") (pin "1") (pinfunction "K_1") (pintype "passive"))
      (node (ref "D7") (pin "2") (pinfunction "A_2") (pintype "passive"))
      (node (ref "J13") (pin "1") (pinfunction "1_1") (pintype "passive"))
      (node (ref "R42") (pin "2") (pinfunction "2_2") (pintype "passive"))
      (node (ref "U6") (pin "11") (pinfunction "PA4_11") (pintype "bidirectional"))
    )
    (net (code "11") (name "/ADC_T_4") (class "Default")
      (node (ref "C38") (pin "2") (pinfunction "2_2") (pintype "passive"))
      (node (ref "D11") (pin "1") (pinfunction "K_1") (pintype "passive"))
      (node (ref "D9") (pin "2") (pinfunction "A_2") (pintype "passive"))
      (node (ref "J12") (pin "1") (pinfunction "1_1") (pintype "passive"))
      (node (ref "R44") (pin "2") (pinfunction "2_2") (pintype "passive"))
      (node (ref "U6") (pin "12") (pinfunction "PA5_12") (pintype "bidirectional"))
    )
    (net (code "12") (name "/ADC_T_5") (class "Default")
      (node (ref "C34") (pin "2") (pinfunction "2_2") (pintype "passive"))
      (node (ref "D5") (pin "2") (pinfunction "A_2") (pintype "passive"))
      (node (ref "D6") (pin "1") (pinfunction "K_1") (pintype "passive"))
      (node (ref "J9") (pin "1") (pinfunction "1_1") (pintype "passive"))
      (node (ref "R35") (pin "2") (pinfunction "2_2") (pintype "passive"))
      (node (ref "U6") (pin "13") (pinfunction "PA6_13") (pintype "bidirectional"))
    )
    (net (code "13") (name "/ADC_U_1") (class "Default")
      (node (ref "C1") (pin "2") (pinfunction "2_2") (pintype "passive"))
      (node (ref "R1") (pin "1") (pinfunction "1_1") (pintype "passive"))
      (node (ref "R14") (pin "1") (pinfunction "1_1") (pintype "passive"))
      (node (ref "U6") (pin "7") (pinfunction "PA0_7") (pintype "bidirectional"))
    )
    (net (code "14") (name "/DIRECT") (class "Default")
      (node (ref "R47") (pin "2") (pinfunction "2_2") (pintype "passive"))
      (node (ref "R48") (pin "2") (pinfunction "2_2") (pintype "passive"))
      (node (ref "TP25") (pin "1") (pinfunction "G9_1") (pintype "passive"))
      (node (ref "U10") (pin "5") (pinfunction "VIC_5") (pintype "input"))
      (node (ref "U6") (pin "2") (pinfunction "PB9/PC14-OSC32_IN_2") (pintype "bidirectional"))
    )
    (net (code "15") (name "/INT_UI") (class "Default")
      (node (ref "D1") (pin "2") (pinfunction "K_2") (pintype "passive"))
      (node (ref "R22") (pin "2") (pinfunction "2_2") (pintype "passive"))
      (node (ref "TP16") (pin "1") (pinfunction "G9_1") (pintype "passive"))
      (node (ref "U6") (pin "15") (pinfunction "PB0/PB1/PB2/PA8_15") (pintype "bidirectional"))
      (node (ref "X3") (pin "1") (pinfunction "1_1") (pintype "passive"))
    )
    (net (code "16") (name "/OUT_N1") (class "Default")
      (node (ref "C17") (pin "1") (pinfunction "1_1") (pintype "passive"))
      (node (ref "R15") (pin "1") (pinfunction "1_1") (pintype "passive"))
      (node (ref "TP13") (pin "1") (pinfunction "G9_1") (pintype "passive"))
      (node (ref "X2") (pin "4") (pinfunction "4_4") (pintype "passive"))
    )
    (net (code "17") (name "/OUT_P1") (class "Default")
      (node (ref "C17") (pin "2") (pinfunction "2_2") (pintype "passive"))
      (node (ref "R11") (pin "1") (pinfunction "1_1") (pintype "passive"))
      (node (ref "TP9") (pin "1") (pinfunction "G9_1") (pintype "passive"))
      (node (ref "X2") (pin "5") (pinfunction "5_5") (pintype "passive"))
    )
    (net (code "18") (name "/RX") (class "Default")
      (node (ref "J8") (pin "5") (pinfunction "5_5") (pintype "passive"))
      (node (ref "R37") (pin "1") (pinfunction "1_1") (pintype "passive"))
      (node (ref "TP28") (pin "1") (pinfunction "G9_1") (pintype "passive"))
      (node (ref "U10") (pin "6") (pinfunction "VOD_6") (pintype "tri_state"))
      (node (ref "U6") (pin "1") (pinfunction "PB7/PB8_1") (pintype "bidirectional"))
    )
    (net (code "19") (name "/SCL") (class "Default")
      (node (ref "R4") (pin "1") (pinfunction "1_1") (pintype "passive"))
      (node (ref "R7") (pin "1") (pinfunction "1_1") (pintype "passive"))
      (node (ref "U6") (pin "16") (pinfunction "PA11[PA9]_16") (pintype "bidirectional"))
      (node (ref "VD1") (pin "2") (pinfunction "C_2") (pintype "passive"))
    )
    (net (code "20") (name "/SDA") (class "Default")
      (node (ref "R10") (pin "1") (pinfunction "1_1") (pintype "passive"))
      (node (ref "R5") (pin "1") (pinfunction "1_1") (pintype "passive"))
      (node (ref "U6") (pin "17") (pinfunction "PA12[PA10]_17") (pintype "bidirectional"))
      (node (ref "VD2") (pin "2") (pinfunction "C_2") (pintype "passive"))
    )
    (net (code "21") (name "/SWCLC") (class "Default")
      (node (ref "J8") (pin "3") (pinfunction "3_3") (pintype "passive"))
      (node (ref "R30") (pin "1") (pinfunction "1_1") (pintype "passive"))
      (node (ref "U6") (pin "19") (pinfunction "PA15/PA14-BOOT0_19") (pintype "bidirectional"))
    )
    (net (code "22") (name "/SWDIO") (class "Default")
      (node (ref "J8") (pin "2") (pinfunction "2_2") (pintype "passive"))
      (node (ref "U6") (pin "18") (pinfunction "PA13_18") (pintype "bidirectional"))
    )
    (net (code "23") (name "/TX") (class "Default")
      (node (ref "J8") (pin "4") (pinfunction "4_4") (pintype "passive"))
      (node (ref "R40") (pin "1") (pinfunction "1_1") (pintype "passive"))
      (node (ref "TP26") (pin "1") (pinfunction "G9_1") (pintype "passive"))
      (node (ref "U10") (pin "4") (pinfunction "VIB_4") (pintype "input"))
      (node (ref "U6") (pin "20") (pinfunction "PB3/PB4/PB5/PB6_20") (pintype "bidirectional"))
    )
    (net (code "24") (name "GND_2") (class "Default")
      (node (ref "C36") (pin "2") (pinfunction "2_2") (pintype "passive"))
      (node (ref "R46") (pin "1") (pinfunction "1_1") (pintype "passive"))
      (node (ref "R49") (pin "1") (pinfunction "1_1") (pintype "passive"))
      (node (ref "TP30") (pin "1") (pinfunction "G9_1") (pintype "passive"))
      (node (ref "U10") (pin "15") (pinfunction "GND2_15") (pintype "power_in"))
      (node (ref "U10") (pin "9") (pinfunction "GND2_9") (pintype "power_in"))
      (node (ref "U8") (pin "3") (pinfunction "0V_3") (pintype "power_in"))
      (node (ref "U9") (pin "5") (pinfunction "GND_5") (pintype "power_in"))
      (node (ref "X4") (pin "2") (pinfunction "2_2") (pintype "passive"))
      (node (ref "ZD2") (pin "1") (pinfunction "A_1") (pintype "passive"))
      (node (ref "ZD3") (pin "1") (pinfunction "A_1") (pintype "passive"))
    )
    (net (code "25") (name "GND_III") (class "Default")
      (node (ref "C1") (pin "1") (pinfunction "1_1") (pintype "passive"))
      (node (ref "C10") (pin "2") (pinfunction "-_2") (pintype "passive"))
      (node (ref "C11") (pin "2") (pinfunction "-_2") (pintype "passive"))
      (node (ref "C12") (pin "2") (pinfunction "-_2") (pintype "passive"))
      (node (ref "C13") (pin "1") (pinfunction "1_1") (pintype "passive"))
      (node (ref "C14") (pin "1") (pinfunction "1_1") (pintype "passive"))
      (node (ref "C18") (pin "1") (pinfunction "1_1") (pintype "passive"))
      (node (ref "C19") (pin "1") (pinfunction "1_1") (pintype "passive"))
      (node (ref "C2") (pin "1") (pinfunction "1_1") (pintype "passive"))
      (node (ref "C21") (pin "1") (pinfunction "1_1") (pintype "passive"))
      (node (ref "C25") (pin "1") (pinfunction "1_1") (pintype "passive"))
      (node (ref "C26") (pin "1") (pinfunction "1_1") (pintype "passive"))
      (node (ref "C27") (pin "2") (pinfunction "2_2") (pintype "passive"))
      (node (ref "C3") (pin "2") (pinfunction "-_2") (pintype "passive"))
      (node (ref "C30") (pin "1") (pinfunction "1_1") (pintype "passive"))
      (node (ref "C31") (pin "1") (pinfunction "1_1") (pintype "passive"))
      (node (ref "C32") (pin "2") (pinfunction "2_2") (pintype "passive"))
      (node (ref "C34") (pin "1") (pinfunction "1_1") (pintype "passive"))
      (node (ref "C37") (pin "1") (pinfunction "1_1") (pintype "passive"))
      (node (ref "C38") (pin "1") (pinfunction "1_1") (pintype "passive"))
      (node (ref "C39") (pin "1") (pinfunction "1_1") (pintype "passive"))
      (node (ref "C4") (pin "2") (pinfunction "-_2") (pintype "passive"))
      (node (ref "C5") (pin "2") (pinfunction "-_2") (pintype "passive"))
      (node (ref "C6") (pin "1") (pinfunction "1_1") (pintype "passive"))
      (node (ref "C7") (pin "1") (pinfunction "1_1") (pintype "passive"))
      (node (ref "C8") (pin "1") (pinfunction "1_1") (pintype "passive"))
      (node (ref "C9") (pin "2") (pinfunction "-_2") (pintype "passive"))
      (node (ref "D10") (pin "2") (pinfunction "A_2") (pintype "passive"))
      (node (ref "D11") (pin "2") (pinfunction "A_2") (pintype "passive"))
      (node (ref "D12") (pin "2") (pinfunction "A_2") (pintype "passive"))
      (node (ref "D13") (pin "2") (pinfunction "K_2") (pintype "passive"))
      (node (ref "D2") (pin "2") (pinfunction "A_2") (pintype "passive"))
      (node (ref "D3") (pin "2") (pinfunction "K_2") (pintype "passive"))
      (node (ref "D4") (pin "2") (pinfunction "K_2") (pintype "passive"))
      (node (ref "D6") (pin "2") (pinfunction "A_2") (pintype "passive"))
      (node (ref "J11") (pin "2") (pinfunction "2_2") (pintype "passive"))
      (node (ref "J12") (pin "2") (pinfunction "2_2") (pintype "passive"))
      (node (ref "J13") (pin "2") (pinfunction "2_2") (pintype "passive"))
      (node (ref "J3") (pin "1") (pinfunction "1_1") (pintype "passive"))
      (node (ref "J8") (pin "6") (pinfunction "6_6") (pintype "passive"))
      (node (ref "J9") (pin "2") (pinfunction "2_2") (pintype "passive"))
      (node (ref "R1") (pin "2") (pinfunction "2_2") (pintype "passive"))
      (node (ref "R16") (pin "2") (pinfunction "2_2") (pintype "passive"))
      (node (ref "R2") (pin "1") (pinfunction "1_1") (pintype "passive"))
      (node (ref "R20") (pin "1") (pinfunction "1_1") (pintype "passive"))
      (node (ref "R30") (pin "2") (pinfunction "2_2") (pintype "passive"))
      (node (ref "R32") (pin "1") (pinfunction "1_1") (pintype "passive"))
      (node (ref "R34") (pin "1") (pinfunction "1_1") (pintype "passive"))
      (node (ref "R48") (pin "1") (pinfunction "1_1") (pintype "passive"))
      (node (ref "TP21") (pin "1") (pinfunction "G9_1") (pintype "passive"))
      (node (ref "TP4") (pin "1") (pinfunction "G9_1") (pintype "passive"))
      (node (ref "U1") (pin "3") (pinfunction "SD_3") (pintype "input"))
      (node (ref "U1") (pin "4") (pinfunction "GND_4") (pintype "power_in"))
      (node (ref "U10") (pin "2") (pinfunction "GND1_2") (pintype "power_in"))
      (node (ref "U10") (pin "8") (pinfunction "GND1_8") (pintype "power_in"))
      (node (ref "U2") (pin "1") (pinfunction "Ground_1") (pintype "power_in"))
      (node (ref "U3") (pin "1") (pinfunction "Ground_1") (pintype "power_in"))
      (node (ref "U5") (pin "2") (pinfunction "VSS_2") (pintype "power_in"))
      (node (ref "U6") (pin "5") (pinfunction "VSS/VSSA_5") (pintype "power_in"))
      (node (ref "U7") (pin "4") (pinfunction "GND_4") (pintype "power_in"))
      (node (ref "U8") (pin "1") (pinfunction "GND_1") (pintype "power_in"))
      (node (ref "VD1") (pin "1") (pinfunction "A_1") (pintype "passive"))
      (node (ref "VD2") (pin "1") (pinfunction "A_1") (pintype "passive"))
      (node (ref "X1") (pin "1") (pinfunction "1_1") (pintype "passive"))
      (node (ref "X1") (pin "2") (pinfunction "2_2") (pintype "passive"))
      (node (ref "X1") (pin "4") (pinfunction "4_4") (pintype "passive"))
      (node (ref "X2") (pin "1") (pinfunction "1_1") (pintype "passive"))
      (node (ref "X2") (pin "2") (pinfunction "2_2") (pintype "passive"))
      (node (ref "X3") (pin "2") (pinfunction "2_2") (pintype "passive"))
      (node (ref "X3") (pin "3") (pinfunction "3_3") (pintype "passive"))
      (node (ref "X5") (pin "1") (pinfunction "1_1") (pintype "passive"))
    )
    (net (code "26") (name "Net-(C4-+)") (class "Default")
      (node (ref "C30") (pin "2") (pinfunction "2_2") (pintype "passive"))
      (node (ref "C4") (pin "1") (pinfunction "+_1") (pintype "passive"))
      (node (ref "L3") (pin "2") (pinfunction "2_2") (pintype "passive"))
      (node (ref "TP19") (pin "1") (pinfunction "G9_1") (pintype "passive"))
      (node (ref "U3") (pin "3") (pinfunction "VIN_3") (pintype "power_in"))
    )
    (net (code "27") (name "Net-(C9-+)") (class "Default")
      (node (ref "C9") (pin "1") (pinfunction "+_1") (pintype "passive"))
      (node (ref "JE1") (pin "1") (pinfunction "1_1") (pintype "passive"))
      (node (ref "L3") (pin "1") (pinfunction "1_1") (pintype "passive"))
      (node (ref "U1") (pin "8") (pinfunction "IN_8") (pintype "power_in"))
    )
    (net (code "28") (name "Net-(C10-+)") (class "Default")
      (node (ref "C10") (pin "1") (pinfunction "+_1") (pintype "passive"))
      (node (ref "JE1") (pin "2") (pinfunction "2_2") (pintype "passive"))
      (node (ref "L2") (pin "2") (pinfunction "2_2") (pintype "passive"))
      (node (ref "R33") (pin "1") (pinfunction "1_1") (pintype "passive"))
    )
    (net (code "29") (name "Net-(C18-Pad2)") (class "Default")
      (node (ref "C18") (pin "2") (pinfunction "2_2") (pintype "passive"))
      (node (ref "R12") (pin "1") (pinfunction "1_1") (pintype "passive"))
      (node (ref "R13") (pin "2") (pinfunction "2_2") (pintype "passive"))
    )
    (net (code "30") (name "Net-(D1-A)") (class "Default")
      (node (ref "D1") (pin "1") (pinfunction "A_1") (pintype "passive"))
      (node (ref "R25") (pin "1") (pinfunction "1_1") (pintype "passive"))
    )
    (net (code "31") (name "Net-(D2-C)") (class "Default")
      (node (ref "D2") (pin "1") (pinfunction "C_1") (pintype "passive"))
      (node (ref "L2") (pin "1") (pinfunction "1_1") (pintype "passive"))
      (node (ref "TP18") (pin "1") (pinfunction "G9_1") (pintype "passive"))
      (node (ref "U7") (pin "2") (pinfunction "SWE_2") (pintype "open_emitter"))
    )
    (net (code "32") (name "Net-(D3-A)") (class "Default")
      (node (ref "D3") (pin "1") (pinfunction "A_1") (pintype "passive"))
      (node (ref "R27") (pin "2") (pinfunction "2_2") (pintype "passive"))
    )
    (net (code "33") (name "Net-(D4-A)") (class "Default")
      (node (ref "D4") (pin "1") (pinfunction "A_1") (pintype "passive"))
      (node (ref "R31") (pin "2") (pinfunction "2_2") (pintype "passive"))
    )
    (net (code "34") (name "Net-(D13-A)") (class "Default")
      (node (ref "D13") (pin "1") (pinfunction "A_1") (pintype "passive"))
      (node (ref "R47") (pin "1") (pinfunction "1_1") (pintype "passive"))
    )
    (net (code "35") (name "Net-(J3-Pad3)") (class "Default")
      (node (ref "J3") (pin "3") (pinfunction "3_3") (pintype "passive"))
      (node (ref "R7") (pin "2") (pinfunction "2_2") (pintype "passive"))
    )
    (net (code "36") (name "Net-(J3-Pad4)") (class "Default")
      (node (ref "J3") (pin "4") (pinfunction "4_4") (pintype "passive"))
      (node (ref "R10") (pin "2") (pinfunction "2_2") (pintype "passive"))
    )
    (net (code "37") (name "Net-(TP10-G9)") (class "Default")
      (node (ref "C16") (pin "2") (pinfunction "2_2") (pintype "passive"))
      (node (ref "C21") (pin "2") (pinfunction "2_2") (pintype "passive"))
      (node (ref "R11") (pin "2") (pinfunction "2_2") (pintype "passive"))
      (node (ref "R20") (pin "2") (pinfunction "2_2") (pintype "passive"))
      (node (ref "TP10") (pin "1") (pinfunction "G9_1") (pintype "passive"))
      (node (ref "U5") (pin "3") (pinfunction "VIN+_3") (pintype "input"))
    )
    (net (code "38") (name "Net-(TP11-G9)") (class "Default")
      (node (ref "C19") (pin "2") (pinfunction "2_2") (pintype "passive"))
      (node (ref "R13") (pin "1") (pinfunction "1_1") (pintype "passive"))
      (node (ref "R14") (pin "2") (pinfunction "2_2") (pintype "passive"))
      (node (ref "R16") (pin "1") (pinfunction "1_1") (pintype "passive"))
      (node (ref "TP11") (pin "1") (pinfunction "G9_1") (pintype "passive"))
    )
    (net (code "39") (name "Net-(TP12-G9)") (class "Default")
      (node (ref "C22") (pin "2") (pinfunction "2_2") (pintype "passive"))
      (node (ref "R12") (pin "2") (pinfunction "2_2") (pintype "passive"))
      (node (ref "R21") (pin "2") (pinfunction "2_2") (pintype "passive"))
      (node (ref "TP12") (pin "1") (pinfunction "G9_1") (pintype "passive"))
      (node (ref "U5") (pin "1") (pinfunction "VOUT_1") (pintype "output"))
    )
    (net (code "40") (name "Net-(TP14-G9)") (class "Default")
      (node (ref "C16") (pin "1") (pinfunction "1_1") (pintype "passive"))
      (node (ref "C22") (pin "1") (pinfunction "1_1") (pintype "passive"))
      (node (ref "R15") (pin "2") (pinfunction "2_2") (pintype "passive"))
      (node (ref "R21") (pin "1") (pinfunction "1_1") (pintype "passive"))
      (node (ref "TP14") (pin "1") (pinfunction "G9_1") (pintype "passive"))
      (node (ref "U5") (pin "4") (pinfunction "VIN-_4") (pintype "input"))
    )
    (net (code "41") (name "Net-(TP24-G9)") (class "Default")
      (node (ref "R38") (pin "1") (pinfunction "1_1") (pintype "passive"))
      (node (ref "R41") (pin "1") (pinfunction "1_1") (pintype "passive"))
      (node (ref "TP24") (pin "1") (pinfunction "G9_1") (pintype "passive"))
      (node (ref "U9") (pin "4") (pinfunction "DI_4") (pintype "input"))
    )
    (net (code "42") (name "Net-(TP27-G9)") (class "Default")
      (node (ref "R46") (pin "2") (pinfunction "2_2") (pintype "passive"))
      (node (ref "TP27") (pin "1") (pinfunction "G9_1") (pintype "passive"))
      (node (ref "U10") (pin "12") (pinfunction "VOC_12") (pintype "tri_state"))
      (node (ref "U9") (pin "2") (pinfunction "~{RE}_2") (pintype "input"))
      (node (ref "U9") (pin "3") (pinfunction "DE_3") (pintype "input"))
    )
    (net (code "43") (name "Net-(TP29-G9)") (class "Default")
      (node (ref "R39") (pin "1") (pinfunction "1_1") (pintype "passive"))
      (node (ref "R45") (pin "1") (pinfunction "1_1") (pintype "passive"))
      (node (ref "TP29") (pin "1") (pinfunction "G9_1") (pintype "passive"))
      (node (ref "U9") (pin "1") (pinfunction "RO_1") (pintype "output"))
    )
    (net (code "44") (name "Net-(U1-FB)") (class "Default")
      (node (ref "U1") (pin "6") (pinfunction "VTAP_6") (pintype "passive"))
      (node (ref "U1") (pin "7") (pinfunction "FB_7") (pintype "input"))
    )
    (net (code "45") (name "Net-(U1-~{ERR})") (class "Default")
      (node (ref "R3") (pin "2") (pinfunction "2_2") (pintype "passive"))
      (node (ref "U1") (pin "5") (pinfunction "~{ERR}_5") (pintype "open_collector"))
    )
    (net (code "46") (name "Net-(U6-PA7)") (class "Default")
      (node (ref "R27") (pin "1") (pinfunction "1_1") (pintype "passive"))
      (node (ref "U6") (pin "14") (pinfunction "PA7_14") (pintype "bidirectional"))
    )
    (net (code "47") (name "Net-(U6-PC15-OSC32_OUT)") (class "Default")
      (node (ref "R31") (pin "1") (pinfunction "1_1") (pintype "passive"))
      (node (ref "U6") (pin "3") (pinfunction "PC15-OSC32_OUT_3") (pintype "bidirectional"))
    )
    (net (code "48") (name "Net-(U6-~{RST})") (class "Default")
      (node (ref "C26") (pin "2") (pinfunction "2_2") (pintype "passive"))
      (node (ref "R26") (pin "2") (pinfunction "2_2") (pintype "passive"))
      (node (ref "U6") (pin "6") (pinfunction "~{RST}_6") (pintype "input"))
    )
    (net (code "49") (name "Net-(U7-CII)") (class "Default")
      (node (ref "R33") (pin "2") (pinfunction "2_2") (pintype "passive"))
      (node (ref "R34") (pin "2") (pinfunction "2_2") (pintype "passive"))
      (node (ref "U7") (pin "5") (pinfunction "CII_5") (pintype "input"))
    )
    (net (code "50") (name "Net-(U7-DRC)") (class "Default")
      (node (ref "R28") (pin "2") (pinfunction "2_2") (pintype "passive"))
      (node (ref "U7") (pin "1") (pinfunction "SWC_1") (pintype "open_collector"))
      (node (ref "U7") (pin "7") (pinfunction "IPK_7") (pintype "passive"))
      (node (ref "U7") (pin "8") (pinfunction "DRC_8") (pintype "open_collector"))
    )
    (net (code "51") (name "Net-(U7-TC)") (class "Default")
      (node (ref "C27") (pin "1") (pinfunction "1_1") (pintype "passive"))
      (node (ref "U7") (pin "3") (pinfunction "TC_3") (pintype "passive"))
    )
    (net (code "52") (name "Net-(U9-A)") (class "Default")
      (node (ref "R36") (pin "1") (pinfunction "1_1") (pintype "passive"))
      (node (ref "U9") (pin "6") (pinfunction "A_6") (pintype "bidirectional"))
      (node (ref "X4") (pin "3") (pinfunction "3_3") (pintype "passive"))
      (node (ref "ZD1") (pin "2") (pinfunction "A_2") (pintype "passive"))
      (node (ref "ZD2") (pin "2") (pinfunction "A_2") (pintype "passive"))
    )
    (net (code "53") (name "Net-(U9-B)") (class "Default")
      (node (ref "R49") (pin "2") (pinfunction "2_2") (pintype "passive"))
      (node (ref "U9") (pin "7") (pinfunction "B_7") (pintype "bidirectional"))
      (node (ref "X4") (pin "1") (pinfunction "1_1") (pintype "passive"))
      (node (ref "ZD1") (pin "1") (pinfunction "A_1") (pintype "passive"))
      (node (ref "ZD3") (pin "2") (pinfunction "A_2") (pintype "passive"))
    )
    (net (code "54") (name "Net-(U10-VID)") (class "Default")
      (node (ref "R45") (pin "2") (pinfunction "2_2") (pintype "passive"))
      (node (ref "U10") (pin "11") (pinfunction "VID_11") (pintype "input"))
    )
    (net (code "55") (name "Net-(U10-VOB)") (class "Default")
      (node (ref "R41") (pin "2") (pinfunction "2_2") (pintype "passive"))
      (node (ref "U10") (pin "13") (pinfunction "VOB_13") (pintype "tri_state"))
    )
    (net (code "56") (name "VCC") (class "Default")
      (node (ref "C12") (pin "1") (pinfunction "+_1") (pintype "passive"))
      (node (ref "C32") (pin "1") (pinfunction "1_1") (pintype "passive"))
      (node (ref "R28") (pin "1") (pinfunction "1_1") (pintype "passive"))
      (node (ref "U7") (pin "6") (pinfunction "VCC_6") (pintype "power_in"))
      (node (ref "X3") (pin "4") (pinfunction "4_4") (pintype "passive"))
      (node (ref "X3") (pin "5") (pinfunction "5_5") (pintype "passive"))
      (node (ref "X5") (pin "2") (pinfunction "2_2") (pintype "passive"))
    )
    (net (code "57") (name "unconnected-(DD1-GND-Pad1)") (class "Default")
      (node (ref "DD1") (pin "1") (pinfunction "GND_1") (pintype "passive"))
    )
    (net (code "58") (name "unconnected-(DD1-SCL-Pad3)") (class "Default")
      (node (ref "DD1") (pin "3") (pinfunction "SCL_3") (pintype "passive"))
    )
    (net (code "59") (name "unconnected-(DD1-SDA-Pad4)") (class "Default")
      (node (ref "DD1") (pin "4") (pinfunction "SDA_4") (pintype "passive"))
    )
    (net (code "60") (name "unconnected-(DD1-VCC-Pad2)") (class "Default")
      (node (ref "DD1") (pin "2") (pinfunction "VCC_2") (pintype "passive"))
    )
    (net (code "61") (name "unconnected-(U10-VIA-Pad3)") (class "Default")
      (node (ref "U10") (pin "3") (pinfunction "VIA_3") (pintype "input"))
    )
    (net (code "62") (name "unconnected-(U10-VOA-Pad14)") (class "Default")
      (node (ref "U10") (pin "14") (pinfunction "VOA_14") (pintype "tri_state"))
    )
  )
)
